# ZET6.net
KiCad netlist of a schematic drawn in Altium Designer
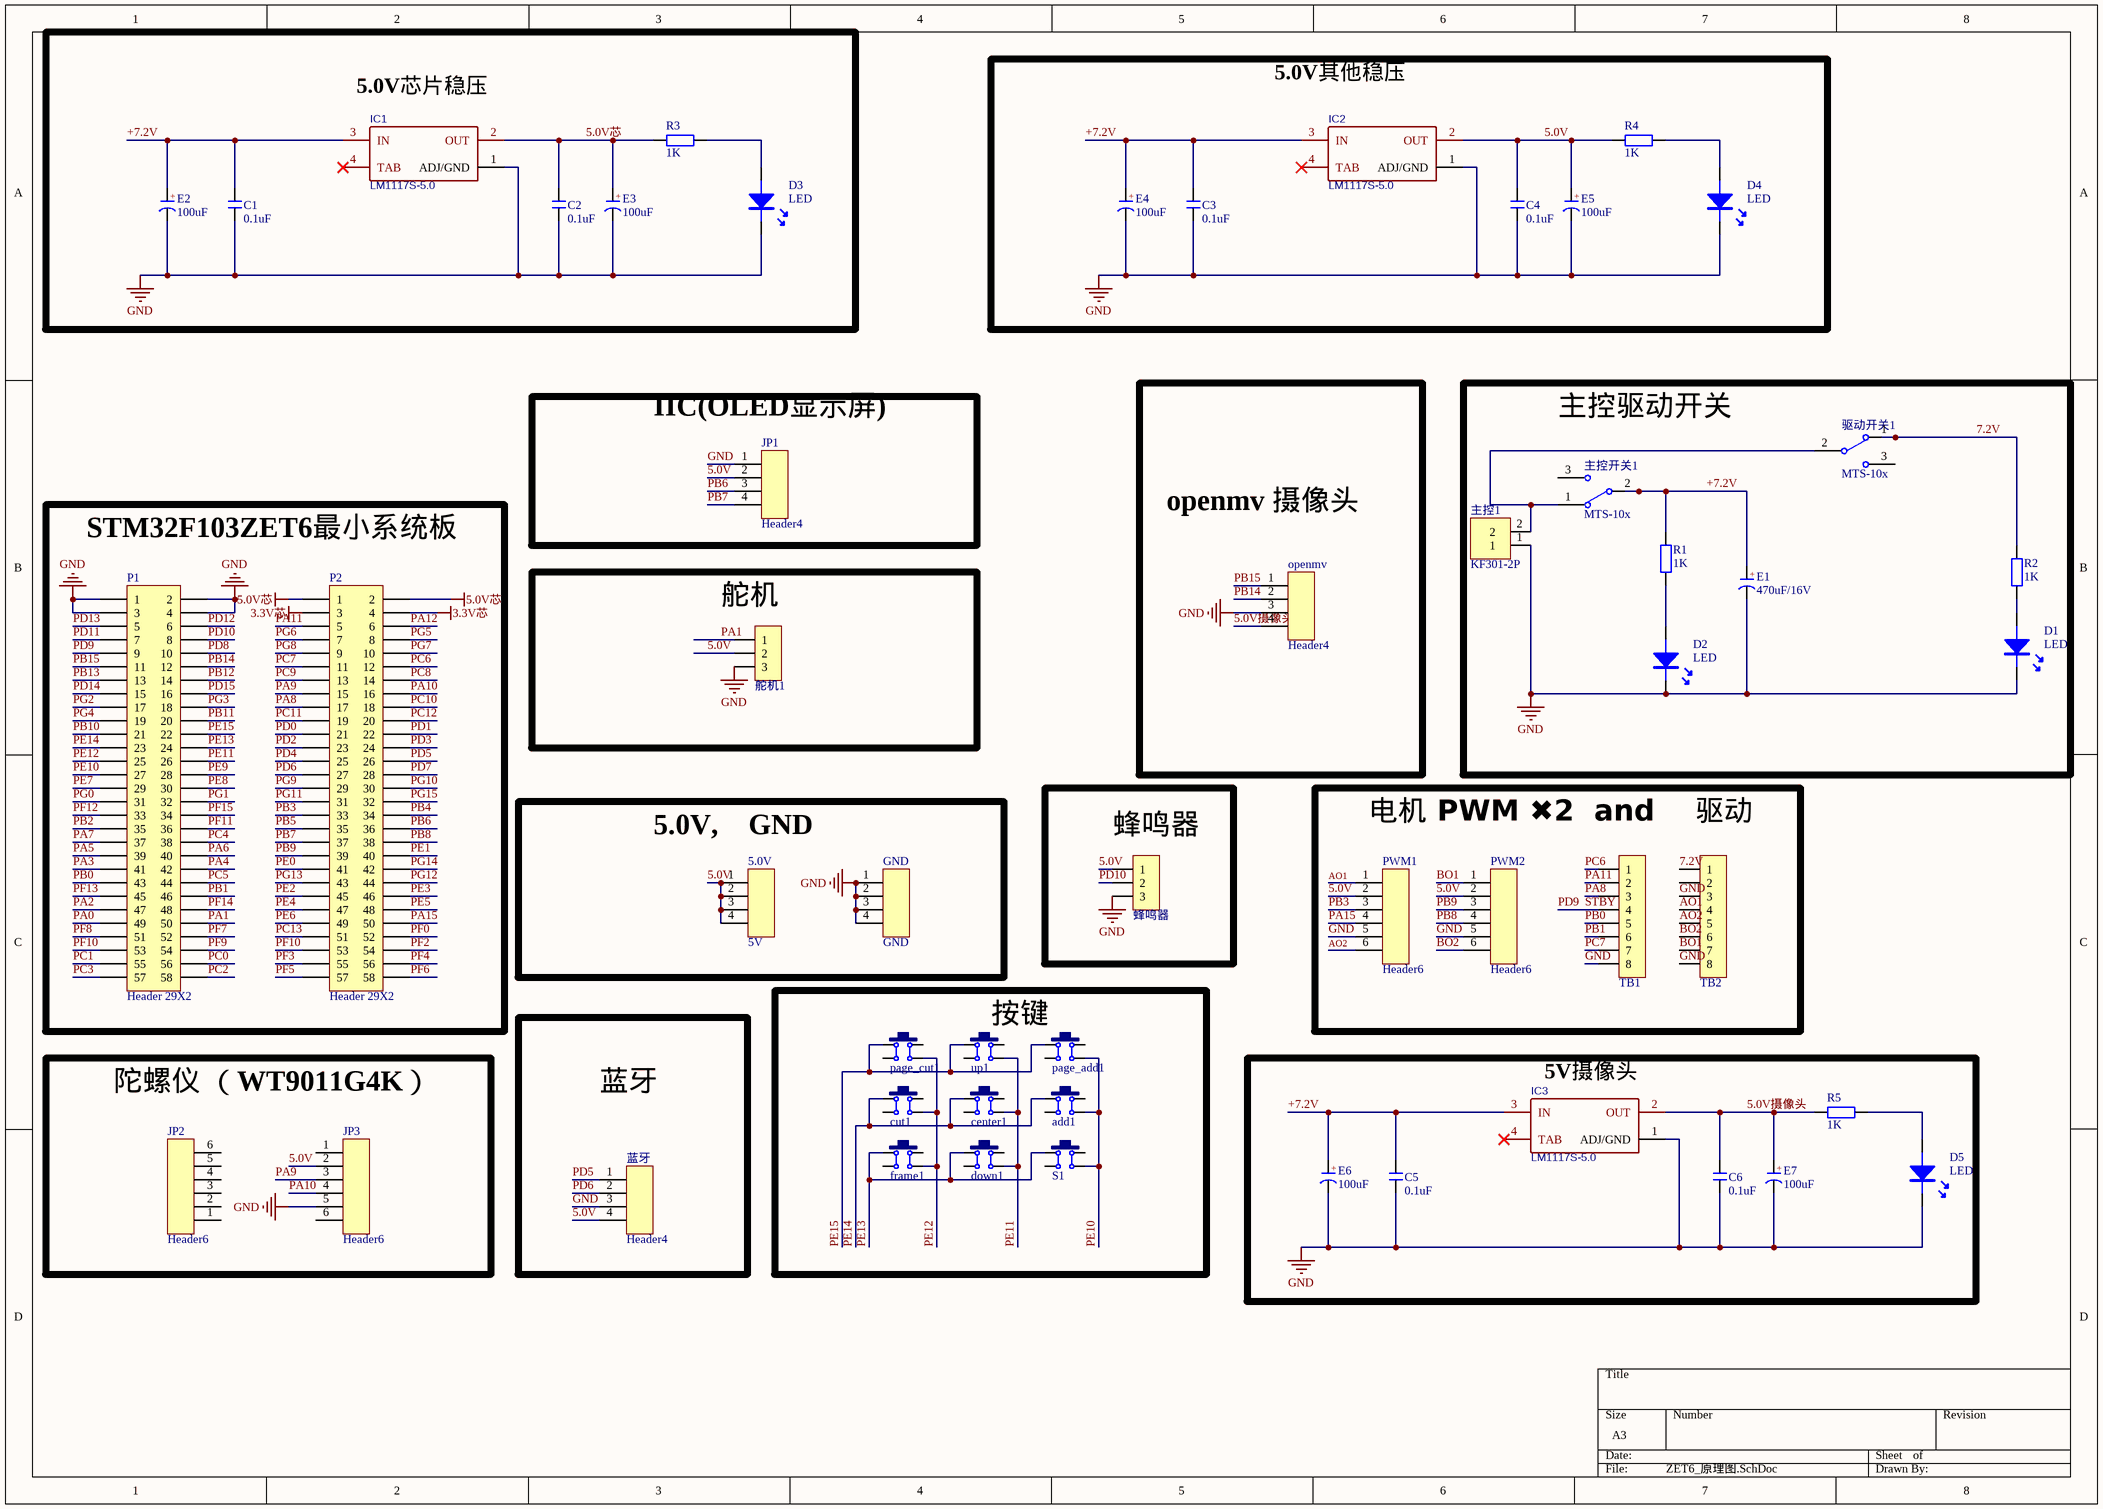
[diagram p0: ZET6_原理图.SchDoc]

(export (version "E")
  (design (tool "Eeschema 10.0.6"))
  (components
    (comp (ref "5.0V") (value "5V") (footprint "JP4") (libsource (lib "飞思卡尔器件库") (part "Header4")))
    (comp (ref "add1")
      (value "6x6x5")
      (footprint "TSW DIP-6*6*6")
      (description "直插6x6轻触开关")
      (fields (field (name "版权归属") "源创客"))
      (libsource (lib "5.1   - 按键-开关") (part "TSW DIP-6x6"))
    )
    (comp (ref "C1")
      (value "0.1uF")
      (footprint "C 0805_M")
      (description "无极性贴片电容")
      (fields (field (name "版权归属") "源创客"))
      (libsource (lib "TC264主控(自制)") (part "C"))
    )
    (comp (ref "C2")
      (value "0.1uF")
      (footprint "C 0805_M")
      (description "无极性贴片电容")
      (fields (field (name "版权归属") "源创客"))
      (libsource (lib "TC264主控(自制)") (part "C"))
    )
    (comp (ref "C3")
      (value "0.1uF")
      (footprint "C 0805_M")
      (description "无极性贴片电容")
      (fields (field (name "版权归属") "源创客"))
      (libsource (lib "TC264主控(自制)") (part "C"))
    )
    (comp (ref "C4")
      (value "0.1uF")
      (footprint "C 0805_M")
      (description "无极性贴片电容")
      (fields (field (name "版权归属") "源创客"))
      (libsource (lib "TC264主控(自制)") (part "C"))
    )
    (comp (ref "C5")
      (value "0.1uF")
      (footprint "C 0805_M")
      (description "无极性贴片电容")
      (fields (field (name "版权归属") "源创客"))
      (libsource (lib "TC264主控(自制)") (part "C"))
    )
    (comp (ref "C6")
      (value "0.1uF")
      (footprint "C 0805_M")
      (description "无极性贴片电容")
      (fields (field (name "版权归属") "源创客"))
      (libsource (lib "TC264主控(自制)") (part "C"))
    )
    (comp (ref "center1")
      (value "6x6x5")
      (footprint "TSW DIP-6*6*6")
      (description "直插6x6轻触开关")
      (fields (field (name "版权归属") "源创客"))
      (libsource (lib "5.1   - 按键-开关") (part "TSW DIP-6x6"))
    )
    (comp (ref "cut1")
      (value "6x6x5")
      (footprint "TSW DIP-6*6*6")
      (description "直插6x6轻触开关")
      (fields (field (name "版权归属") "源创客"))
      (libsource (lib "5.1   - 按键-开关") (part "TSW DIP-6x6"))
    )
    (comp (ref "D1") (value "LED") (footprint "LED-0805B") (libsource (lib "LED") (part "LED")))
    (comp (ref "D2") (value "LED") (footprint "LED-0805B") (libsource (lib "LED") (part "LED")))
    (comp (ref "D3") (value "LED") (footprint "LED-0805R") (libsource (lib "LED") (part "LED")))
    (comp (ref "D4") (value "LED") (footprint "LED-0805R") (libsource (lib "LED") (part "LED")))
    (comp (ref "D5") (value "LED") (footprint "LED-0805R") (libsource (lib "LED") (part "LED")))
    (comp (ref "down1")
      (value "6x6x5")
      (footprint "TSW DIP-6*6*6")
      (description "直插6x6轻触开关")
      (fields (field (name "版权归属") "源创客"))
      (libsource (lib "5.1   - 按键-开关") (part "TSW DIP-6x6"))
    )
    (comp (ref "E1")
      (value "470uF/16V")
      (footprint "CAP 2.5*6.3*11.2 - BK")
      (description "直插电解电容")
      (fields (field (name "版权归属") "源创客"))
      (libsource (lib "3.1   - 电阻-电容-电感") (part "C-CAP"))
    )
    (comp (ref "E2")
      (value "100uF")
      (footprint "CD A(3216)")
      (description "贴片钽电容")
      (fields (field (name "版权归属") "源创客"))
      (libsource (lib "TC264主控(自制)") (part "C-CD"))
    )
    (comp (ref "E3")
      (value "100uF")
      (footprint "CD A(3216)")
      (description "贴片钽电容")
      (fields (field (name "版权归属") "源创客"))
      (libsource (lib "TC264主控(自制)") (part "C-CD"))
    )
    (comp (ref "E4")
      (value "100uF")
      (footprint "CD A(3216)")
      (description "贴片钽电容")
      (fields (field (name "版权归属") "源创客"))
      (libsource (lib "TC264主控(自制)") (part "C-CD"))
    )
    (comp (ref "E5")
      (value "100uF")
      (footprint "CD A(3216)")
      (description "贴片钽电容")
      (fields (field (name "版权归属") "源创客"))
      (libsource (lib "TC264主控(自制)") (part "C-CD"))
    )
    (comp (ref "E6")
      (value "100uF")
      (footprint "CD A(3216)")
      (description "贴片钽电容")
      (fields (field (name "版权归属") "源创客"))
      (libsource (lib "TC264主控(自制)") (part "C-CD"))
    )
    (comp (ref "E7")
      (value "100uF")
      (footprint "CD A(3216)")
      (description "贴片钽电容")
      (fields (field (name "版权归属") "源创客"))
      (libsource (lib "TC264主控(自制)") (part "C-CD"))
    )
    (comp (ref "frame1")
      (value "6x6x5")
      (footprint "TSW DIP-6*6*6")
      (description "直插6x6轻触开关")
      (fields (field (name "版权归属") "源创客"))
      (libsource (lib "5.1   - 按键-开关") (part "TSW DIP-6x6"))
    )
    (comp (ref "GND") (value "GND") (footprint "JP4") (libsource (lib "飞思卡尔器件库") (part "Header4")))
    (comp (ref "IC1")
      (value "LM1117S-5.0")
      (footprint "SOT-223-3_L6.5-W3.4-P2.30-LS7.0-BR")
      (fields (field (name "BOM_SUPPLIER PART") "C126028"))
      (libsource (lib "TC264主控(自制)") (part "LM1117S-5.0"))
    )
    (comp (ref "IC2")
      (value "LM1117S-5.0")
      (footprint "SOT-223-3_L6.5-W3.4-P2.30-LS7.0-BR")
      (fields (field (name "BOM_SUPPLIER PART") "C126028"))
      (libsource (lib "TC264主控(自制)") (part "LM1117S-5.0"))
    )
    (comp (ref "IC3")
      (value "LM1117S-5.0")
      (footprint "SOT-223-3_L6.5-W3.4-P2.30-LS7.0-BR")
      (fields (field (name "BOM_SUPPLIER PART") "C126028"))
      (libsource (lib "TC264主控(自制)") (part "LM1117S-5.0"))
    )
    (comp (ref "JP1") (value "Header4") (footprint "JP4") (libsource (lib "飞思卡尔器件库") (part "Header4")))
    (comp (ref "JP2") (value "Header6") (footprint "JP6") (libsource (lib "") (part "Header6_1")))
    (comp (ref "JP3") (value "Header6") (footprint "JP6") (libsource (lib "飞思卡尔器件库") (part "Header6")))
    (comp (ref "openmv") (value "Header4") (footprint "JP4") (libsource (lib "飞思卡尔器件库") (part "Header4")))
    (comp (ref "P1") (value "Header 29X2") (footprint "HDR2X29") (libsource (lib "元件库") (part "Header 29X2")))
    (comp (ref "P2") (value "Header 29X2") (footprint "HDR2X29") (libsource (lib "元件库") (part "Header 29X2")))
    (comp (ref "page_add1")
      (value "6x6x5")
      (footprint "TSW DIP-6*6*6")
      (description "直插6x6轻触开关")
      (fields (field (name "版权归属") "源创客"))
      (libsource (lib "5.1   - 按键-开关") (part "TSW DIP-6x6"))
    )
    (comp (ref "page_cut1")
      (value "6x6x5")
      (footprint "TSW DIP-6*6*6")
      (description "直插6x6轻触开关")
      (fields (field (name "版权归属") "源创客"))
      (libsource (lib "5.1   - 按键-开关") (part "TSW DIP-6x6"))
    )
    (comp (ref "PWM1") (value "Header6") (footprint "JP6") (libsource (lib "飞思卡尔器件库") (part "Header6")))
    (comp (ref "PWM2") (value "Header6") (footprint "JP6") (libsource (lib "飞思卡尔器件库") (part "Header6")))
    (comp (ref "R1")
      (value "1K")
      (footprint "R 0805_M")
      (description "贴片电阻")
      (fields (field (name "版权归属") "源创客"))
      (libsource (lib "3.1   - 电阻-电容-电感") (part "R"))
    )
    (comp (ref "R2")
      (value "1K")
      (footprint "R 0805_M")
      (description "贴片电阻")
      (fields (field (name "版权归属") "源创客"))
      (libsource (lib "3.1   - 电阻-电容-电感") (part "R"))
    )
    (comp (ref "R3")
      (value "1K")
      (footprint "R 0805_L")
      (description "贴片电阻")
      (fields (field (name "版权归属") "源创客"))
      (libsource (lib "3.1   - 电阻-电容-电感") (part "R"))
    )
    (comp (ref "R4")
      (value "1K")
      (footprint "R 0805_L")
      (description "贴片电阻")
      (fields (field (name "版权归属") "源创客"))
      (libsource (lib "3.1   - 电阻-电容-电感") (part "R"))
    )
    (comp (ref "R5")
      (value "1K")
      (footprint "R 0805_L")
      (description "贴片电阻")
      (fields (field (name "版权归属") "源创客"))
      (libsource (lib "3.1   - 电阻-电容-电感") (part "R"))
    )
    (comp (ref "S1")
      (value "6x6x5")
      (footprint "TSW DIP-6*6*6")
      (description "直插6x6轻触开关")
      (fields (field (name "版权归属") "源创客"))
      (libsource (lib "5.1   - 按键-开关") (part "TSW DIP-6x6"))
    )
    (comp (ref "TB1")
      (value "HDR-1X8")
      (footprint "JP8")
      (description "8P接插件")
      (fields (field (name "版权归属") "源创客"))
      (libsource (lib "4.5   - 接插件-脚距2.54") (part "Header 8"))
    )
    (comp (ref "TB2")
      (value "HDR-1X8")
      (footprint "JP8")
      (description "8P接插件")
      (fields (field (name "版权归属") "源创客"))
      (libsource (lib "4.5   - 接插件-脚距2.54") (part "Header 8"))
    )
    (comp (ref "up1")
      (value "6x6x5")
      (footprint "TSW DIP-6*6*6")
      (description "直插6x6轻触开关")
      (fields (field (name "版权归属") "源创客"))
      (libsource (lib "5.1   - 按键-开关") (part "TSW DIP-6x6"))
    )
    (comp (ref "主控1")
      (value "KF301-2P")
      (footprint "KF301-5.0-2P")
      (description "KF301插座")
      (fields (field (name "版权所属") "go home"))
      (libsource (lib "1.5   - 未分类芯片-系统板") (part "KF301-2P"))
    )
    (comp (ref "主控开关1")
      (value "MTS-10x")
      (footprint "SS-12D10")
      (description "MTS10x系列3脚扭子开关")
      (fields (field (name "版权归属") "源创客"))
      (libsource (lib "5.1   - 按键-开关") (part "MTS-10x"))
    )
    (comp (ref "舵机1")
      (value "HDR-1X3")
      (footprint "jp3")
      (description "3P接插件")
      (fields (field (name "版权归属") "源创客"))
      (libsource (lib "4.5   - 接插件-脚距2.54") (part "Header 3"))
    )
    (comp (ref "蓝牙") (value "Header4") (footprint "JP4") (libsource (lib "飞思卡尔器件库") (part "Header4")))
    (comp (ref "蜂鸣器")
      (value "HDR-1X3")
      (footprint "JP3")
      (description "3P接插件")
      (fields (field (name "版权归属") "源创客"))
      (libsource (lib "4.5   - 接插件-脚距2.54") (part "Header 3"))
    )
    (comp (ref "驱动开关1")
      (value "MTS-10x")
      (footprint "KFT DIP-7X7")
      (description "MTS10x系列3脚扭子开关")
      (fields (field (name "版权归属") "源创客"))
      (libsource (lib "5.1   - 按键-开关") (part "MTS-10x"))
    )
  )
  (nets
    (net (code "1") (name "/+7.2V") (class "Default")
      (node (ref "C1") (pin "2") (pinfunction "2_2") (pintype "passive"))
      (node (ref "C3") (pin "2") (pinfunction "2_2") (pintype "passive"))
      (node (ref "C5") (pin "2") (pinfunction "2_2") (pintype "passive"))
      (node (ref "E1") (pin "1") (pinfunction "A_1") (pintype "passive"))
      (node (ref "E2") (pin "1") (pinfunction "A_1") (pintype "passive"))
      (node (ref "E4") (pin "1") (pinfunction "A_1") (pintype "passive"))
      (node (ref "E6") (pin "1") (pinfunction "A_1") (pintype "passive"))
      (node (ref "IC1") (pin "3") (pinfunction "IN_3") (pintype "passive"))
      (node (ref "IC2") (pin "3") (pinfunction "IN_3") (pintype "passive"))
      (node (ref "IC3") (pin "3") (pinfunction "IN_3") (pintype "passive"))
      (node (ref "R1") (pin "2") (pinfunction "2_2") (pintype "passive"))
      (node (ref "主控开关1") (pin "2") (pinfunction "2_2") (pintype "passive"))
    )
    (net (code "2") (name "/5.0V") (class "Default")
      (node (ref "5.0V") (pin "1") (pinfunction "1_1") (pintype "passive"))
      (node (ref "5.0V") (pin "2") (pinfunction "2_2") (pintype "passive"))
      (node (ref "5.0V") (pin "3") (pinfunction "3_3") (pintype "passive"))
      (node (ref "5.0V") (pin "4") (pinfunction "4_4") (pintype "passive"))
      (node (ref "C4") (pin "2") (pinfunction "2_2") (pintype "passive"))
      (node (ref "E5") (pin "1") (pinfunction "A_1") (pintype "passive"))
      (node (ref "IC2") (pin "2") (pinfunction "OUT_2") (pintype "passive"))
      (node (ref "JP1") (pin "2") (pinfunction "2_2") (pintype "passive"))
      (node (ref "JP3") (pin "2") (pinfunction "2_2") (pintype "passive"))
      (node (ref "PWM1") (pin "2") (pinfunction "2_2") (pintype "passive"))
      (node (ref "PWM2") (pin "2") (pinfunction "2_2") (pintype "passive"))
      (node (ref "R4") (pin "1") (pinfunction "1_1") (pintype "passive"))
      (node (ref "舵机1") (pin "2") (pinfunction "2_2") (pintype "passive"))
      (node (ref "蓝牙") (pin "4") (pinfunction "4_4") (pintype "passive"))
      (node (ref "蜂鸣器") (pin "1") (pinfunction "1_1") (pintype "passive"))
    )
    (net (code "3") (name "/5.0V摄像头") (class "Default")
      (node (ref "C6") (pin "2") (pinfunction "2_2") (pintype "passive"))
      (node (ref "E7") (pin "1") (pinfunction "A_1") (pintype "passive"))
      (node (ref "IC3") (pin "2") (pinfunction "OUT_2") (pintype "passive"))
      (node (ref "R5") (pin "1") (pinfunction "1_1") (pintype "passive"))
      (node (ref "openmv") (pin "4") (pinfunction "4_4") (pintype "passive"))
    )
    (net (code "4") (name "/7.2V") (class "Default")
      (node (ref "R2") (pin "2") (pinfunction "2_2") (pintype "passive"))
      (node (ref "TB2") (pin "1") (pinfunction "1_1") (pintype "passive"))
      (node (ref "驱动开关1") (pin "1") (pinfunction "1_1") (pintype "passive"))
    )
    (net (code "5") (name "/AO1") (class "Default")
      (node (ref "PWM1") (pin "1") (pinfunction "1_1") (pintype "passive"))
      (node (ref "TB2") (pin "4") (pinfunction "4_4") (pintype "passive"))
    )
    (net (code "6") (name "/AO2") (class "Default")
      (node (ref "PWM1") (pin "6") (pinfunction "6_6") (pintype "passive"))
      (node (ref "TB2") (pin "5") (pinfunction "5_5") (pintype "passive"))
    )
    (net (code "7") (name "/BO1") (class "Default")
      (node (ref "PWM2") (pin "1") (pinfunction "1_1") (pintype "passive"))
      (node (ref "TB2") (pin "7") (pinfunction "7_7") (pintype "passive"))
    )
    (net (code "8") (name "/BO2") (class "Default")
      (node (ref "PWM2") (pin "6") (pinfunction "6_6") (pintype "passive"))
      (node (ref "TB2") (pin "6") (pinfunction "6_6") (pintype "passive"))
    )
    (net (code "9") (name "/PA0") (class "Default")
      (node (ref "P1") (pin "49") (pinfunction "49_49") (pintype "passive"))
    )
    (net (code "10") (name "/PA1") (class "Default")
      (node (ref "P1") (pin "50") (pinfunction "50_50") (pintype "passive"))
      (node (ref "舵机1") (pin "1") (pinfunction "1_1") (pintype "passive"))
    )
    (net (code "11") (name "/PA2") (class "Default")
      (node (ref "P1") (pin "47") (pinfunction "47_47") (pintype "passive"))
    )
    (net (code "12") (name "/PA3") (class "Default")
      (node (ref "P1") (pin "41") (pinfunction "41_41") (pintype "passive"))
    )
    (net (code "13") (name "/PA4") (class "Default")
      (node (ref "P1") (pin "42") (pinfunction "42_42") (pintype "passive"))
    )
    (net (code "14") (name "/PA5") (class "Default")
      (node (ref "P1") (pin "39") (pinfunction "39_39") (pintype "passive"))
    )
    (net (code "15") (name "/PA6") (class "Default")
      (node (ref "P1") (pin "40") (pinfunction "40_40") (pintype "passive"))
    )
    (net (code "16") (name "/PA7") (class "Default")
      (node (ref "P1") (pin "37") (pinfunction "37_37") (pintype "passive"))
    )
    (net (code "17") (name "/PA8") (class "Default")
      (node (ref "P2") (pin "17") (pinfunction "17_17") (pintype "passive"))
      (node (ref "TB1") (pin "3") (pinfunction "3_3") (pintype "passive"))
    )
    (net (code "18") (name "/PA9") (class "Default")
      (node (ref "JP3") (pin "3") (pinfunction "3_3") (pintype "passive"))
      (node (ref "P2") (pin "15") (pinfunction "15_15") (pintype "passive"))
    )
    (net (code "19") (name "/PA10") (class "Default")
      (node (ref "JP3") (pin "4") (pinfunction "4_4") (pintype "passive"))
      (node (ref "P2") (pin "16") (pinfunction "16_16") (pintype "passive"))
    )
    (net (code "20") (name "/PA11") (class "Default")
      (node (ref "P2") (pin "5") (pinfunction "5_5") (pintype "passive"))
      (node (ref "TB1") (pin "2") (pinfunction "2_2") (pintype "passive"))
    )
    (net (code "21") (name "/PA12") (class "Default")
      (node (ref "P2") (pin "6") (pinfunction "6_6") (pintype "passive"))
    )
    (net (code "22") (name "/PA15") (class "Default")
      (node (ref "P2") (pin "50") (pinfunction "50_50") (pintype "passive"))
      (node (ref "PWM1") (pin "4") (pinfunction "4_4") (pintype "passive"))
    )
    (net (code "23") (name "/PB0") (class "Default")
      (node (ref "P1") (pin "43") (pinfunction "43_43") (pintype "passive"))
      (node (ref "TB1") (pin "5") (pinfunction "5_5") (pintype "passive"))
    )
    (net (code "24") (name "/PB1") (class "Default")
      (node (ref "P1") (pin "46") (pinfunction "46_46") (pintype "passive"))
      (node (ref "TB1") (pin "6") (pinfunction "6_6") (pintype "passive"))
    )
    (net (code "25") (name "/PB2") (class "Default")
      (node (ref "P1") (pin "35") (pinfunction "35_35") (pintype "passive"))
    )
    (net (code "26") (name "/PB3") (class "Default")
      (node (ref "P2") (pin "33") (pinfunction "33_33") (pintype "passive"))
      (node (ref "PWM1") (pin "3") (pinfunction "3_3") (pintype "passive"))
    )
    (net (code "27") (name "/PB4") (class "Default")
      (node (ref "P2") (pin "34") (pinfunction "34_34") (pintype "passive"))
    )
    (net (code "28") (name "/PB5") (class "Default")
      (node (ref "P2") (pin "35") (pinfunction "35_35") (pintype "passive"))
    )
    (net (code "29") (name "/PB6") (class "Default")
      (node (ref "JP1") (pin "3") (pinfunction "3_3") (pintype "passive"))
      (node (ref "P2") (pin "36") (pinfunction "36_36") (pintype "passive"))
    )
    (net (code "30") (name "/PB7") (class "Default")
      (node (ref "JP1") (pin "4") (pinfunction "4_4") (pintype "passive"))
      (node (ref "P2") (pin "37") (pinfunction "37_37") (pintype "passive"))
    )
    (net (code "31") (name "/PB8") (class "Default")
      (node (ref "P2") (pin "38") (pinfunction "38_38") (pintype "passive"))
      (node (ref "PWM2") (pin "4") (pinfunction "4_4") (pintype "passive"))
    )
    (net (code "32") (name "/PB9") (class "Default")
      (node (ref "P2") (pin "39") (pinfunction "39_39") (pintype "passive"))
      (node (ref "PWM2") (pin "3") (pinfunction "3_3") (pintype "passive"))
    )
    (net (code "33") (name "/PB10") (class "Default")
      (node (ref "P1") (pin "21") (pinfunction "21_21") (pintype "passive"))
    )
    (net (code "34") (name "/PB11") (class "Default")
      (node (ref "P1") (pin "20") (pinfunction "20_20") (pintype "passive"))
    )
    (net (code "35") (name "/PB12") (class "Default")
      (node (ref "P1") (pin "14") (pinfunction "14_14") (pintype "passive"))
    )
    (net (code "36") (name "/PB13") (class "Default")
      (node (ref "P1") (pin "13") (pinfunction "13_13") (pintype "passive"))
    )
    (net (code "37") (name "/PB14") (class "Default")
      (node (ref "P1") (pin "12") (pinfunction "12_12") (pintype "passive"))
      (node (ref "openmv") (pin "2") (pinfunction "2_2") (pintype "passive"))
    )
    (net (code "38") (name "/PB15") (class "Default")
      (node (ref "P1") (pin "11") (pinfunction "11_11") (pintype "passive"))
      (node (ref "openmv") (pin "1") (pinfunction "1_1") (pintype "passive"))
    )
    (net (code "39") (name "/PC0") (class "Default")
      (node (ref "P1") (pin "56") (pinfunction "56_56") (pintype "passive"))
    )
    (net (code "40") (name "/PC1") (class "Default")
      (node (ref "P1") (pin "55") (pinfunction "55_55") (pintype "passive"))
    )
    (net (code "41") (name "/PC2") (class "Default")
      (node (ref "P1") (pin "58") (pinfunction "58_58") (pintype "passive"))
    )
    (net (code "42") (name "/PC3") (class "Default")
      (node (ref "P1") (pin "57") (pinfunction "57_57") (pintype "passive"))
    )
    (net (code "43") (name "/PC4") (class "Default")
      (node (ref "P1") (pin "38") (pinfunction "38_38") (pintype "passive"))
    )
    (net (code "44") (name "/PC5") (class "Default")
      (node (ref "P1") (pin "44") (pinfunction "44_44") (pintype "passive"))
    )
    (net (code "45") (name "/PC6") (class "Default")
      (node (ref "P2") (pin "12") (pinfunction "12_12") (pintype "passive"))
      (node (ref "TB1") (pin "1") (pinfunction "1_1") (pintype "passive"))
    )
    (net (code "46") (name "/PC7") (class "Default")
      (node (ref "P2") (pin "11") (pinfunction "11_11") (pintype "passive"))
      (node (ref "TB1") (pin "7") (pinfunction "7_7") (pintype "passive"))
    )
    (net (code "47") (name "/PC8") (class "Default")
      (node (ref "P2") (pin "14") (pinfunction "14_14") (pintype "passive"))
    )
    (net (code "48") (name "/PC9") (class "Default")
      (node (ref "P2") (pin "13") (pinfunction "13_13") (pintype "passive"))
    )
    (net (code "49") (name "/PC10") (class "Default")
      (node (ref "P2") (pin "18") (pinfunction "18_18") (pintype "passive"))
    )
    (net (code "50") (name "/PC11") (class "Default")
      (node (ref "P2") (pin "19") (pinfunction "19_19") (pintype "passive"))
    )
    (net (code "51") (name "/PC12") (class "Default")
      (node (ref "P2") (pin "20") (pinfunction "20_20") (pintype "passive"))
    )
    (net (code "52") (name "/PC13") (class "Default")
      (node (ref "P2") (pin "51") (pinfunction "51_51") (pintype "passive"))
    )
    (net (code "53") (name "/PD0") (class "Default")
      (node (ref "P2") (pin "21") (pinfunction "21_21") (pintype "passive"))
    )
    (net (code "54") (name "/PD1") (class "Default")
      (node (ref "P2") (pin "22") (pinfunction "22_22") (pintype "passive"))
    )
    (net (code "55") (name "/PD2") (class "Default")
      (node (ref "P2") (pin "23") (pinfunction "23_23") (pintype "passive"))
    )
    (net (code "56") (name "/PD3") (class "Default")
      (node (ref "P2") (pin "24") (pinfunction "24_24") (pintype "passive"))
    )
    (net (code "57") (name "/PD4") (class "Default")
      (node (ref "P2") (pin "25") (pinfunction "25_25") (pintype "passive"))
    )
    (net (code "58") (name "/PD5") (class "Default")
      (node (ref "P2") (pin "26") (pinfunction "26_26") (pintype "passive"))
      (node (ref "蓝牙") (pin "1") (pinfunction "1_1") (pintype "passive"))
    )
    (net (code "59") (name "/PD6") (class "Default")
      (node (ref "P2") (pin "27") (pinfunction "27_27") (pintype "passive"))
      (node (ref "蓝牙") (pin "2") (pinfunction "2_2") (pintype "passive"))
    )
    (net (code "60") (name "/PD7") (class "Default")
      (node (ref "P2") (pin "28") (pinfunction "28_28") (pintype "passive"))
    )
    (net (code "61") (name "/PD8") (class "Default")
      (node (ref "P1") (pin "10") (pinfunction "10_10") (pintype "passive"))
    )
    (net (code "62") (name "/PD9") (class "Default")
      (node (ref "P1") (pin "9") (pinfunction "9_9") (pintype "passive"))
      (node (ref "TB1") (pin "4") (pinfunction "4_4") (pintype "passive"))
    )
    (net (code "63") (name "/PD10") (class "Default")
      (node (ref "P1") (pin "8") (pinfunction "8_8") (pintype "passive"))
      (node (ref "蜂鸣器") (pin "2") (pinfunction "2_2") (pintype "passive"))
    )
    (net (code "64") (name "/PD11") (class "Default")
      (node (ref "P1") (pin "7") (pinfunction "7_7") (pintype "passive"))
    )
    (net (code "65") (name "/PD12") (class "Default")
      (node (ref "P1") (pin "6") (pinfunction "6_6") (pintype "passive"))
    )
    (net (code "66") (name "/PD13") (class "Default")
      (node (ref "P1") (pin "5") (pinfunction "5_5") (pintype "passive"))
    )
    (net (code "67") (name "/PD14") (class "Default")
      (node (ref "P1") (pin "15") (pinfunction "15_15") (pintype "passive"))
    )
    (net (code "68") (name "/PD15") (class "Default")
      (node (ref "P1") (pin "16") (pinfunction "16_16") (pintype "passive"))
    )
    (net (code "69") (name "/PE0") (class "Default")
      (node (ref "P2") (pin "41") (pinfunction "41_41") (pintype "passive"))
    )
    (net (code "70") (name "/PE1") (class "Default")
      (node (ref "P2") (pin "40") (pinfunction "40_40") (pintype "passive"))
    )
    (net (code "71") (name "/PE2") (class "Default")
      (node (ref "P2") (pin "45") (pinfunction "45_45") (pintype "passive"))
    )
    (net (code "72") (name "/PE3") (class "Default")
      (node (ref "P2") (pin "46") (pinfunction "46_46") (pintype "passive"))
    )
    (net (code "73") (name "/PE4") (class "Default")
      (node (ref "P2") (pin "47") (pinfunction "47_47") (pintype "passive"))
    )
    (net (code "74") (name "/PE5") (class "Default")
      (node (ref "P2") (pin "48") (pinfunction "48_48") (pintype "passive"))
    )
    (net (code "75") (name "/PE6") (class "Default")
      (node (ref "P2") (pin "49") (pinfunction "49_49") (pintype "passive"))
    )
    (net (code "76") (name "/PE7") (class "Default")
      (node (ref "P1") (pin "29") (pinfunction "29_29") (pintype "passive"))
    )
    (net (code "77") (name "/PE8") (class "Default")
      (node (ref "P1") (pin "30") (pinfunction "30_30") (pintype "passive"))
    )
    (net (code "78") (name "/PE9") (class "Default")
      (node (ref "P1") (pin "28") (pinfunction "28_28") (pintype "passive"))
    )
    (net (code "79") (name "/PE10") (class "Default")
      (node (ref "P1") (pin "27") (pinfunction "27_27") (pintype "passive"))
      (node (ref "S1") (pin "3") (pinfunction "3_3") (pintype "passive"))
      (node (ref "add1") (pin "3") (pinfunction "3_3") (pintype "passive"))
      (node (ref "page_add1") (pin "3") (pinfunction "3_3") (pintype "passive"))
    )
    (net (code "80") (name "/PE11") (class "Default")
      (node (ref "P1") (pin "26") (pinfunction "26_26") (pintype "passive"))
      (node (ref "center1") (pin "3") (pinfunction "3_3") (pintype "passive"))
      (node (ref "down1") (pin "3") (pinfunction "3_3") (pintype "passive"))
      (node (ref "up1") (pin "3") (pinfunction "3_3") (pintype "passive"))
    )
    (net (code "81") (name "/PE12") (class "Default")
      (node (ref "P1") (pin "25") (pinfunction "25_25") (pintype "passive"))
      (node (ref "cut1") (pin "3") (pinfunction "3_3") (pintype "passive"))
      (node (ref "frame1") (pin "3") (pinfunction "3_3") (pintype "passive"))
      (node (ref "page_cut1") (pin "3") (pinfunction "3_3") (pintype "passive"))
    )
    (net (code "82") (name "/PE13") (class "Default")
      (node (ref "P1") (pin "24") (pinfunction "24_24") (pintype "passive"))
      (node (ref "S1") (pin "1") (pinfunction "1_1") (pintype "passive"))
      (node (ref "down1") (pin "1") (pinfunction "1_1") (pintype "passive"))
      (node (ref "frame1") (pin "1") (pinfunction "1_1") (pintype "passive"))
    )
    (net (code "83") (name "/PE14") (class "Default")
      (node (ref "P1") (pin "23") (pinfunction "23_23") (pintype "passive"))
      (node (ref "add1") (pin "1") (pinfunction "1_1") (pintype "passive"))
      (node (ref "center1") (pin "1") (pinfunction "1_1") (pintype "passive"))
      (node (ref "cut1") (pin "1") (pinfunction "1_1") (pintype "passive"))
    )
    (net (code "84") (name "/PE15") (class "Default")
      (node (ref "P1") (pin "22") (pinfunction "22_22") (pintype "passive"))
      (node (ref "page_add1") (pin "1") (pinfunction "1_1") (pintype "passive"))
      (node (ref "page_cut1") (pin "1") (pinfunction "1_1") (pintype "passive"))
      (node (ref "up1") (pin "1") (pinfunction "1_1") (pintype "passive"))
    )
    (net (code "85") (name "/PF0") (class "Default")
      (node (ref "P2") (pin "52") (pinfunction "52_52") (pintype "passive"))
    )
    (net (code "86") (name "/PF2") (class "Default")
      (node (ref "P2") (pin "54") (pinfunction "54_54") (pintype "passive"))
    )
    (net (code "87") (name "/PF3") (class "Default")
      (node (ref "P2") (pin "55") (pinfunction "55_55") (pintype "passive"))
    )
    (net (code "88") (name "/PF4") (class "Default")
      (node (ref "P2") (pin "56") (pinfunction "56_56") (pintype "passive"))
    )
    (net (code "89") (name "/PF5") (class "Default")
      (node (ref "P2") (pin "57") (pinfunction "57_57") (pintype "passive"))
    )
    (net (code "90") (name "/PF6") (class "Default")
      (node (ref "P2") (pin "58") (pinfunction "58_58") (pintype "passive"))
    )
    (net (code "91") (name "/PF7") (class "Default")
      (node (ref "P1") (pin "52") (pinfunction "52_52") (pintype "passive"))
    )
    (net (code "92") (name "/PF8") (class "Default")
      (node (ref "P1") (pin "51") (pinfunction "51_51") (pintype "passive"))
    )
    (net (code "93") (name "/PF9") (class "Default")
      (node (ref "P1") (pin "54") (pinfunction "54_54") (pintype "passive"))
    )
    (net (code "94") (name "/PF10") (class "Default")
      (node (ref "P1") (pin "53") (pinfunction "53_53") (pintype "passive"))
      (node (ref "P2") (pin "53") (pinfunction "53_53") (pintype "passive"))
    )
    (net (code "95") (name "/PF11") (class "Default")
      (node (ref "P1") (pin "36") (pinfunction "36_36") (pintype "passive"))
    )
    (net (code "96") (name "/PF12") (class "Default")
      (node (ref "P1") (pin "33") (pinfunction "33_33") (pintype "passive"))
    )
    (net (code "97") (name "/PF13") (class "Default")
      (node (ref "P1") (pin "45") (pinfunction "45_45") (pintype "passive"))
    )
    (net (code "98") (name "/PF14") (class "Default")
      (node (ref "P1") (pin "48") (pinfunction "48_48") (pintype "passive"))
    )
    (net (code "99") (name "/PF15") (class "Default")
      (node (ref "P1") (pin "34") (pinfunction "34_34") (pintype "passive"))
    )
    (net (code "100") (name "/PG0") (class "Default")
      (node (ref "P1") (pin "31") (pinfunction "31_31") (pintype "passive"))
    )
    (net (code "101") (name "/PG1") (class "Default")
      (node (ref "P1") (pin "32") (pinfunction "32_32") (pintype "passive"))
    )
    (net (code "102") (name "/PG2") (class "Default")
      (node (ref "P1") (pin "17") (pinfunction "17_17") (pintype "passive"))
    )
    (net (code "103") (name "/PG3") (class "Default")
      (node (ref "P1") (pin "18") (pinfunction "18_18") (pintype "passive"))
    )
    (net (code "104") (name "/PG4") (class "Default")
      (node (ref "P1") (pin "19") (pinfunction "19_19") (pintype "passive"))
    )
    (net (code "105") (name "/PG5") (class "Default")
      (node (ref "P2") (pin "8") (pinfunction "8_8") (pintype "passive"))
    )
    (net (code "106") (name "/PG6") (class "Default")
      (node (ref "P2") (pin "7") (pinfunction "7_7") (pintype "passive"))
    )
    (net (code "107") (name "/PG7") (class "Default")
      (node (ref "P2") (pin "10") (pinfunction "10_10") (pintype "passive"))
    )
    (net (code "108") (name "/PG8") (class "Default")
      (node (ref "P2") (pin "9") (pinfunction "9_9") (pintype "passive"))
    )
    (net (code "109") (name "/PG9") (class "Default")
      (node (ref "P2") (pin "29") (pinfunction "29_29") (pintype "passive"))
    )
    (net (code "110") (name "/PG10") (class "Default")
      (node (ref "P2") (pin "30") (pinfunction "30_30") (pintype "passive"))
    )
    (net (code "111") (name "/PG11") (class "Default")
      (node (ref "P2") (pin "31") (pinfunction "31_31") (pintype "passive"))
    )
    (net (code "112") (name "/PG12") (class "Default")
      (node (ref "P2") (pin "44") (pinfunction "44_44") (pintype "passive"))
    )
    (net (code "113") (name "/PG13") (class "Default")
      (node (ref "P2") (pin "43") (pinfunction "43_43") (pintype "passive"))
    )
    (net (code "114") (name "/PG14") (class "Default")
      (node (ref "P2") (pin "42") (pinfunction "42_42") (pintype "passive"))
    )
    (net (code "115") (name "/PG15") (class "Default")
      (node (ref "P2") (pin "32") (pinfunction "32_32") (pintype "passive"))
    )
    (net (code "116") (name "3.3V芯") (class "Default")
      (node (ref "P2") (pin "3") (pinfunction "3_3") (pintype "passive"))
      (node (ref "P2") (pin "4") (pinfunction "4_4") (pintype "passive"))
    )
    (net (code "117") (name "5.0V芯") (class "Default")
      (node (ref "C2") (pin "2") (pinfunction "2_2") (pintype "passive"))
      (node (ref "E3") (pin "1") (pinfunction "A_1") (pintype "passive"))
      (node (ref "IC1") (pin "2") (pinfunction "OUT_2") (pintype "passive"))
      (node (ref "P2") (pin "1") (pinfunction "1_1") (pintype "passive"))
      (node (ref "P2") (pin "2") (pinfunction "2_2") (pintype "passive"))
      (node (ref "R3") (pin "1") (pinfunction "1_1") (pintype "passive"))
    )
    (net (code "118") (name "GND") (class "Default")
      (node (ref "C1") (pin "1") (pinfunction "1_1") (pintype "passive"))
      (node (ref "C2") (pin "1") (pinfunction "1_1") (pintype "passive"))
      (node (ref "C3") (pin "1") (pinfunction "1_1") (pintype "passive"))
      (node (ref "C4") (pin "1") (pinfunction "1_1") (pintype "passive"))
      (node (ref "C5") (pin "1") (pinfunction "1_1") (pintype "passive"))
      (node (ref "C6") (pin "1") (pinfunction "1_1") (pintype "passive"))
      (node (ref "D1") (pin "K") (pinfunction "K_K") (pintype "passive"))
      (node (ref "D2") (pin "K") (pinfunction "K_K") (pintype "passive"))
      (node (ref "D3") (pin "K") (pinfunction "K_K") (pintype "passive"))
      (node (ref "D4") (pin "K") (pinfunction "K_K") (pintype "passive"))
      (node (ref "D5") (pin "K") (pinfunction "K_K") (pintype "passive"))
      (node (ref "E1") (pin "2") (pinfunction "K_2") (pintype "passive"))
      (node (ref "E2") (pin "2") (pinfunction "K_2") (pintype "passive"))
      (node (ref "E3") (pin "2") (pinfunction "K_2") (pintype "passive"))
      (node (ref "E4") (pin "2") (pinfunction "K_2") (pintype "passive"))
      (node (ref "E5") (pin "2") (pinfunction "K_2") (pintype "passive"))
      (node (ref "E6") (pin "2") (pinfunction "K_2") (pintype "passive"))
      (node (ref "E7") (pin "2") (pinfunction "K_2") (pintype "passive"))
      (node (ref "GND") (pin "1") (pinfunction "1_1") (pintype "passive"))
      (node (ref "GND") (pin "2") (pinfunction "2_2") (pintype "passive"))
      (node (ref "GND") (pin "3") (pinfunction "3_3") (pintype "passive"))
      (node (ref "GND") (pin "4") (pinfunction "4_4") (pintype "passive"))
      (node (ref "IC1") (pin "1") (pinfunction "ADJ/GND_1") (pintype "passive"))
      (node (ref "IC2") (pin "1") (pinfunction "ADJ/GND_1") (pintype "passive"))
      (node (ref "IC3") (pin "1") (pinfunction "ADJ/GND_1") (pintype "passive"))
      (node (ref "JP1") (pin "1") (pinfunction "1_1") (pintype "passive"))
      (node (ref "JP3") (pin "5") (pinfunction "5_5") (pintype "passive"))
      (node (ref "P1") (pin "1") (pinfunction "1_1") (pintype "passive"))
      (node (ref "P1") (pin "2") (pinfunction "2_2") (pintype "passive"))
      (node (ref "P1") (pin "3") (pinfunction "3_3") (pintype "passive"))
      (node (ref "P1") (pin "4") (pinfunction "4_4") (pintype "passive"))
      (node (ref "PWM1") (pin "5") (pinfunction "5_5") (pintype "passive"))
      (node (ref "PWM2") (pin "5") (pinfunction "5_5") (pintype "passive"))
      (node (ref "TB1") (pin "8") (pinfunction "8_8") (pintype "passive"))
      (node (ref "TB2") (pin "3") (pinfunction "3_3") (pintype "passive"))
      (node (ref "TB2") (pin "8") (pinfunction "8_8") (pintype "passive"))
      (node (ref "openmv") (pin "3") (pinfunction "3_3") (pintype "passive"))
      (node (ref "主控1") (pin "1") (pinfunction "1_1") (pintype "passive"))
      (node (ref "舵机1") (pin "3") (pinfunction "3_3") (pintype "passive"))
      (node (ref "蓝牙") (pin "3") (pinfunction "3_3") (pintype "passive"))
      (node (ref "蜂鸣器") (pin "3") (pinfunction "3_3") (pintype "passive"))
    )
    (net (code "119") (name "Net-(D1-PadA)") (class "Default")
      (node (ref "D1") (pin "A") (pinfunction "A_A") (pintype "passive"))
      (node (ref "R2") (pin "1") (pinfunction "1_1") (pintype "passive"))
    )
    (net (code "120") (name "Net-(D2-PadA)") (class "Default")
      (node (ref "D2") (pin "A") (pinfunction "A_A") (pintype "passive"))
      (node (ref "R1") (pin "1") (pinfunction "1_1") (pintype "passive"))
    )
    (net (code "121") (name "Net-(D3-PadA)") (class "Default")
      (node (ref "D3") (pin "A") (pinfunction "A_A") (pintype "passive"))
      (node (ref "R3") (pin "2") (pinfunction "2_2") (pintype "passive"))
    )
    (net (code "122") (name "Net-(D4-PadA)") (class "Default")
      (node (ref "D4") (pin "A") (pinfunction "A_A") (pintype "passive"))
      (node (ref "R4") (pin "2") (pinfunction "2_2") (pintype "passive"))
    )
    (net (code "123") (name "Net-(D5-PadA)") (class "Default")
      (node (ref "D5") (pin "A") (pinfunction "A_A") (pintype "passive"))
      (node (ref "R5") (pin "2") (pinfunction "2_2") (pintype "passive"))
    )
    (net (code "124") (name "Net-(主控1-Pad2)") (class "Default")
      (node (ref "主控1") (pin "2") (pinfunction "2_2") (pintype "passive"))
      (node (ref "主控开关1") (pin "1") (pinfunction "1_1") (pintype "passive"))
      (node (ref "驱动开关1") (pin "2") (pinfunction "2_2") (pintype "passive"))
    )
    (net (code "125") (name "unconnected-(IC1-TAB-Pad4)") (class "Default")
      (node (ref "IC1") (pin "4") (pinfunction "TAB_4") (pintype "passive+no_connect"))
    )
    (net (code "126") (name "unconnected-(IC2-TAB-Pad4)") (class "Default")
      (node (ref "IC2") (pin "4") (pinfunction "TAB_4") (pintype "passive+no_connect"))
    )
    (net (code "127") (name "unconnected-(IC3-TAB-Pad4)") (class "Default")
      (node (ref "IC3") (pin "4") (pinfunction "TAB_4") (pintype "passive+no_connect"))
    )
    (net (code "128") (name "unconnected-(JP2-Pad1)") (class "Default")
      (node (ref "JP2") (pin "1") (pinfunction "1_1") (pintype "passive"))
    )
    (net (code "129") (name "unconnected-(JP2-Pad2)") (class "Default")
      (node (ref "JP2") (pin "2") (pinfunction "2_2") (pintype "passive"))
    )
    (net (code "130") (name "unconnected-(JP2-Pad3)") (class "Default")
      (node (ref "JP2") (pin "3") (pinfunction "3_3") (pintype "passive"))
    )
    (net (code "131") (name "unconnected-(JP2-Pad4)") (class "Default")
      (node (ref "JP2") (pin "4") (pinfunction "4_4") (pintype "passive"))
    )
    (net (code "132") (name "unconnected-(JP2-Pad5)") (class "Default")
      (node (ref "JP2") (pin "5") (pinfunction "5_5") (pintype "passive"))
    )
    (net (code "133") (name "unconnected-(JP2-Pad6)") (class "Default")
      (node (ref "JP2") (pin "6") (pinfunction "6_6") (pintype "passive"))
    )
    (net (code "134") (name "unconnected-(JP3-Pad1)") (class "Default")
      (node (ref "JP3") (pin "1") (pinfunction "1_1") (pintype "passive"))
    )
    (net (code "135") (name "unconnected-(JP3-Pad6)") (class "Default")
      (node (ref "JP3") (pin "6") (pinfunction "6_6") (pintype "passive"))
    )
    (net (code "136") (name "unconnected-(S1-Pad2)") (class "Default")
      (node (ref "S1") (pin "2") (pinfunction "2_2") (pintype "passive"))
    )
    (net (code "137") (name "unconnected-(S1-Pad4)") (class "Default")
      (node (ref "S1") (pin "4") (pinfunction "4_4") (pintype "passive"))
    )
    (net (code "138") (name "unconnected-(TB2-Pad2)") (class "Default")
      (node (ref "TB2") (pin "2") (pinfunction "2_2") (pintype "passive"))
    )
    (net (code "139") (name "unconnected-(add1-Pad2)") (class "Default")
      (node (ref "add1") (pin "2") (pinfunction "2_2") (pintype "passive"))
    )
    (net (code "140") (name "unconnected-(add1-Pad4)") (class "Default")
      (node (ref "add1") (pin "4") (pinfunction "4_4") (pintype "passive"))
    )
    (net (code "141") (name "unconnected-(center1-Pad2)") (class "Default")
      (node (ref "center1") (pin "2") (pinfunction "2_2") (pintype "passive"))
    )
    (net (code "142") (name "unconnected-(center1-Pad4)") (class "Default")
      (node (ref "center1") (pin "4") (pinfunction "4_4") (pintype "passive"))
    )
    (net (code "143") (name "unconnected-(cut1-Pad2)") (class "Default")
      (node (ref "cut1") (pin "2") (pinfunction "2_2") (pintype "passive"))
    )
    (net (code "144") (name "unconnected-(cut1-Pad4)") (class "Default")
      (node (ref "cut1") (pin "4") (pinfunction "4_4") (pintype "passive"))
    )
    (net (code "145") (name "unconnected-(down1-Pad2)") (class "Default")
      (node (ref "down1") (pin "2") (pinfunction "2_2") (pintype "passive"))
    )
    (net (code "146") (name "unconnected-(down1-Pad4)") (class "Default")
      (node (ref "down1") (pin "4") (pinfunction "4_4") (pintype "passive"))
    )
    (net (code "147") (name "unconnected-(frame1-Pad2)") (class "Default")
      (node (ref "frame1") (pin "2") (pinfunction "2_2") (pintype "passive"))
    )
    (net (code "148") (name "unconnected-(frame1-Pad4)") (class "Default")
      (node (ref "frame1") (pin "4") (pinfunction "4_4") (pintype "passive"))
    )
    (net (code "149") (name "unconnected-(page_add1-Pad2)") (class "Default")
      (node (ref "page_add1") (pin "2") (pinfunction "2_2") (pintype "passive"))
    )
    (net (code "150") (name "unconnected-(page_add1-Pad4)") (class "Default")
      (node (ref "page_add1") (pin "4") (pinfunction "4_4") (pintype "passive"))
    )
    (net (code "151") (name "unconnected-(page_cut1-Pad2)") (class "Default")
      (node (ref "page_cut1") (pin "2") (pinfunction "2_2") (pintype "passive"))
    )
    (net (code "152") (name "unconnected-(page_cut1-Pad4)") (class "Default")
      (node (ref "page_cut1") (pin "4") (pinfunction "4_4") (pintype "passive"))
    )
    (net (code "153") (name "unconnected-(up1-Pad2)") (class "Default")
      (node (ref "up1") (pin "2") (pinfunction "2_2") (pintype "passive"))
    )
    (net (code "154") (name "unconnected-(up1-Pad4)") (class "Default")
      (node (ref "up1") (pin "4") (pinfunction "4_4") (pintype "passive"))
    )
    (net (code "155") (name "unconnected-(主控开关1-Pad3)") (class "Default")
      (node (ref "主控开关1") (pin "3") (pinfunction "3_3") (pintype "passive"))
    )
    (net (code "156") (name "unconnected-(驱动开关1-Pad3)") (class "Default")
      (node (ref "驱动开关1") (pin "3") (pinfunction "3_3") (pintype "passive"))
    )
  )
)
